# Rectifier.net
KiCad netlist of a schematic drawn in Altium Designer
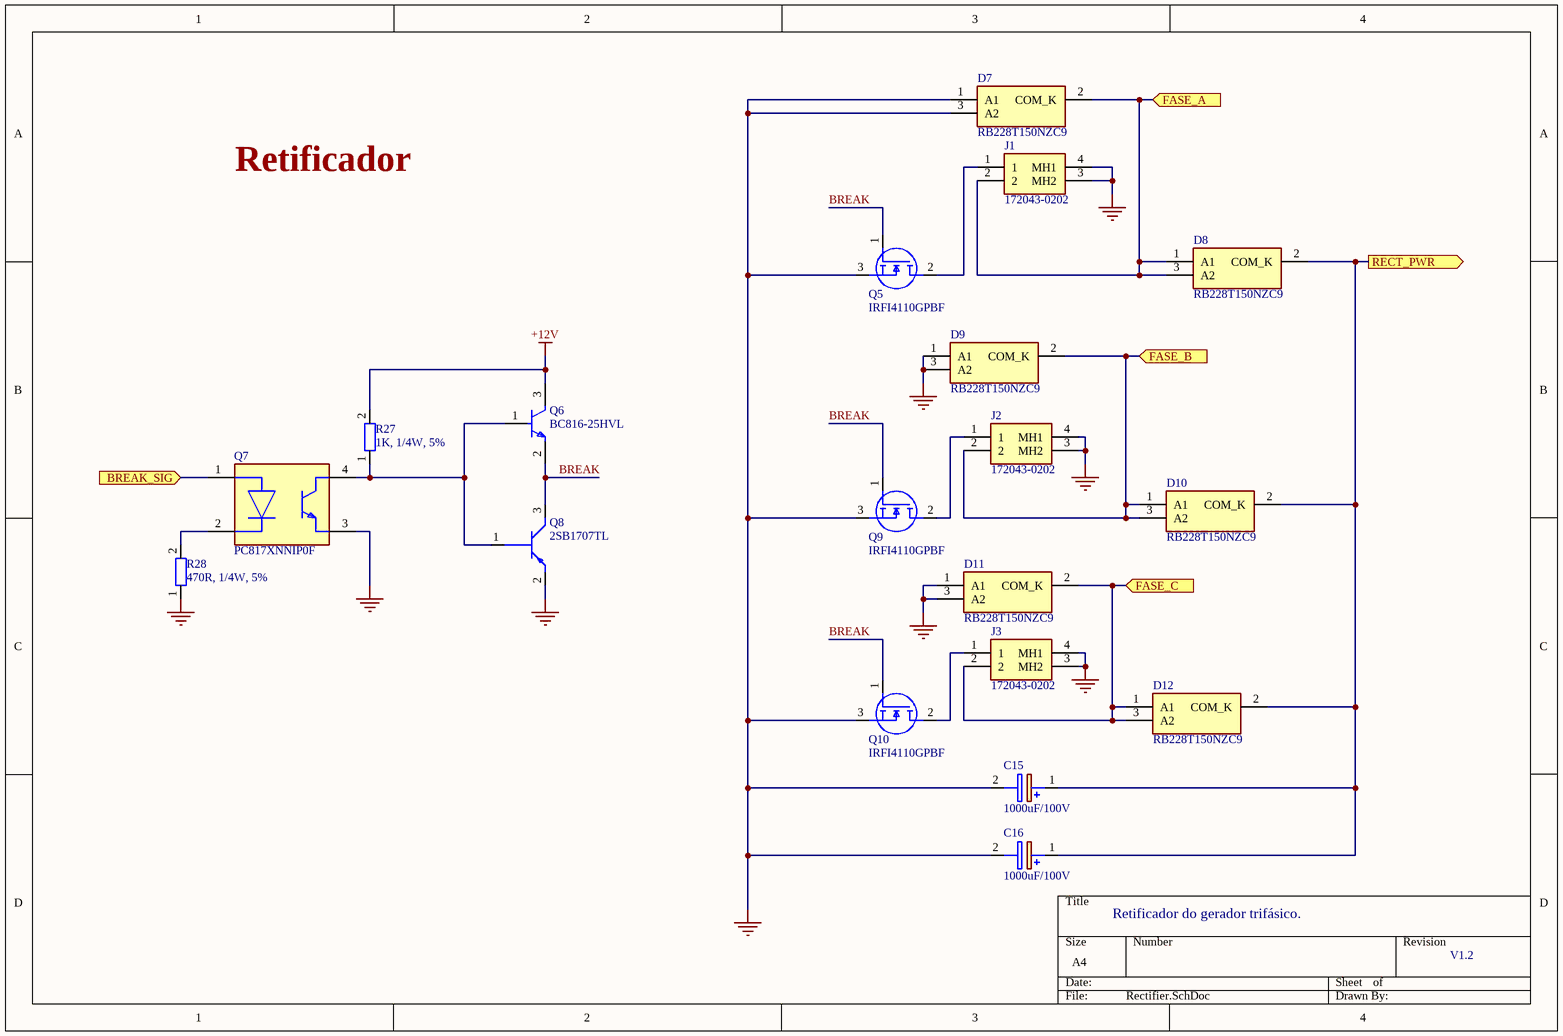
[diagram p0: Rectifier.SchDoc]

(export (version "E")
  (design (tool "Eeschema 10.0.6"))
  (components
    (comp (ref "C15")
      (value "1000uF/100V")
      (footprint "PcbLib1:CAPPRD750W85D1800H3750")
      (description "Aluminum Electrolytic Capacitors - Leaded 1000uF 100V")
      (fields
        (field (name "MANUFACTURER_PART_NUMBER") "ECA-2AHG102")
        (field (name "MOUSER PART NUMBER") "667-ECA-2AHG102")
      )
      (libsource (lib "*") (part "ECA-2AHG102"))
    )
    (comp (ref "C16")
      (value "1000uF/100V")
      (footprint "PcbLib1:CAPPRD750W85D1800H3750")
      (description "Aluminum Electrolytic Capacitors - Leaded 1000uF 100V")
      (fields
        (field (name "MANUFACTURER_PART_NUMBER") "ECA-2AHG102")
        (field (name "MOUSER PART NUMBER") "667-ECA-2AHG102")
      )
      (libsource (lib "*") (part "ECA-2AHG102"))
    )
    (comp (ref "D7")
      (value "RB228T150NZC9")
      (footprint "PcbLib1:TO254P480X1010X2100-3P")
      (description "Schottky Diode")
      (fields (field (name "MANUFACTURER") "Rohm"))
      (libsource (lib "pi2") (part "RB228T150NZC9"))
    )
    (comp (ref "D8")
      (value "RB228T150NZC9")
      (footprint "PcbLib1:TO254P480X1010X2100-3P")
      (description "Schottky Diode")
      (fields (field (name "MANUFACTURER") "Rohm"))
      (libsource (lib "pi2") (part "RB228T150NZC9"))
    )
    (comp (ref "D9")
      (value "RB228T150NZC9")
      (footprint "PcbLib1:TO254P480X1010X2100-3P")
      (description "Schottky Diode")
      (fields (field (name "MANUFACTURER") "Rohm"))
      (libsource (lib "pi2") (part "RB228T150NZC9"))
    )
    (comp (ref "D10")
      (value "RB228T150NZC9")
      (footprint "PcbLib1:TO254P480X1010X2100-3P")
      (description "Schottky Diode")
      (fields (field (name "MANUFACTURER") "Rohm"))
      (libsource (lib "pi2") (part "RB228T150NZC9"))
    )
    (comp (ref "D11")
      (value "RB228T150NZC9")
      (footprint "PcbLib1:TO254P480X1010X2100-3P")
      (description "Schottky Diode")
      (fields (field (name "MANUFACTURER") "Rohm"))
      (libsource (lib "pi2") (part "RB228T150NZC9"))
    )
    (comp (ref "D12")
      (value "RB228T150NZC9")
      (footprint "PcbLib1:TO254P480X1010X2100-3P")
      (description "Schottky Diode")
      (fields (field (name "MANUFACTURER") "Rohm"))
      (libsource (lib "pi2") (part "RB228T150NZC9"))
    )
    (comp (ref "J1")
      (value "172043-0202")
      (footprint "PcbLib1:1720430202")
      (description "CONN HDR 2POS 7.50MM R/A SLDR")
      (fields (field (name "MOUSER PART NUMBER") "538-172043-0202") (field (name "MANUFACTURER") "Molex"))
      (libsource (lib "pi2") (part "172043-0202"))
    )
    (comp (ref "J2")
      (value "172043-0202")
      (footprint "PcbLib1:1720430202")
      (description "CONN HDR 2POS 7.50MM R/A SLDR")
      (fields (field (name "MOUSER PART NUMBER") "538-172043-0202") (field (name "MANUFACTURER") "Molex"))
      (libsource (lib "pi2") (part "172043-0202"))
    )
    (comp (ref "J3")
      (value "172043-0202")
      (footprint "PcbLib1:1720430202")
      (description "CONN HDR 2POS 7.50MM R/A SLDR")
      (fields (field (name "MOUSER PART NUMBER") "538-172043-0202") (field (name "MANUFACTURER") "Molex"))
      (libsource (lib "pi2") (part "172043-0202"))
    )
    (comp (ref "Q5")
      (value "IRFI4110GPBF")
      (footprint "PcbLib1:TO254P483X1018X2095-3P")
      (description "MOSFET N-CH 100V 72A TO220AB")
      (fields (field (name "MOUSER PART NUMBER") "942-IRFI4110GPBF") (field (name "MANUFACTURER") "Infineon"))
      (libsource (lib "*") (part "IRFI4110GPBF"))
    )
    (comp (ref "Q6")
      (value "BC816-25HVL")
      (footprint "FP-SOT23-IPC_C")
      (description "BC816-25H/SOT23/TO-236AB")
      (fields (field (name "MANUFACTURER") "Nexperia"))
      (libsource (lib "Altium Content Vault") (part "9d60fdc623e8f58b3f4e6ee889b877a"))
    )
    (comp (ref "Q7")
      (value "PC817XNNIP0F")
      (footprint "FP-PC817XNNIP0F-MFG")
      (description "OPTOISOLATOR 5KV TRANS 4SMD")
      (fields (field (name "MANUFACTURER") "Sharp"))
      (libsource (lib "Altium Content Vault") (part "6470904bf6395c62928ee73e60120b8"))
    )
    (comp (ref "Q8")
      (value "2SB1707TL")
      (footprint "PcbLib1:SOT95P280X100-3N")
      (description "TRANS PNP 12V 4A TSMT3")
      (fields (field (name "MOUSER PART NUMBER") "755-2SB1707TL") (field (name "MANUFACTURER") "Rohm"))
      (libsource (lib "pi2") (part "2SB1707TL"))
    )
    (comp (ref "Q9")
      (value "IRFI4110GPBF")
      (footprint "PcbLib1:TO254P483X1018X2095-3P")
      (description "MOSFET N-CH 100V 72A TO220AB")
      (fields (field (name "MOUSER PART NUMBER") "942-IRFI4110GPBF") (field (name "MANUFACTURER") "Infineon"))
      (libsource (lib "*") (part "IRFI4110GPBF"))
    )
    (comp (ref "Q10")
      (value "IRFI4110GPBF")
      (footprint "PcbLib1:TO254P483X1018X2095-3P")
      (description "MOSFET N-CH 100V 72A TO220AB")
      (fields (field (name "MOUSER PART NUMBER") "942-IRFI4110GPBF") (field (name "MANUFACTURER") "Infineon"))
      (libsource (lib "*") (part "IRFI4110GPBF"))
    )
    (comp (ref "R27")
      (value "1K, 1/4W, 5%")
      (footprint "PcbLib1:RES-0805")
      (description "Res General Purpose Thick Film 0805 1k Ohm 5% 1/4W ±200ppm/°C Molded Paper T/R")
      (fields
        (field (name "MANUFACTURER_PART_NUMBER") "RC0805JR-131KL")
        (field (name "MOUSER PART NUMBER") "603-RC0805JR-131KL")
      )
      (libsource (lib "pi2") (part "Res-0805"))
    )
    (comp (ref "R28")
      (value "470R, 1/4W, 5%")
      (footprint "PcbLib1:RES-0805")
      (description "Thick Film Resistors - SMD 470 OHM 5%")
      (fields
        (field (name "MANUFACTURER_PART_NUMBER") "RC0805JR-131KL")
        (field (name "MOUSER PART NUMBER") "603-RC0805JR-131KL")
      )
      (libsource (lib "pi2") (part "Res-0805"))
    )
  )
  (nets
    (net (code "1") (name "+12V") (class "Default")
      (node (ref "Q6") (pin "3") (pinfunction "C_3") (pintype "passive"))
      (node (ref "R27") (pin "2") (pinfunction "2_2") (pintype "passive"))
    )
    (net (code "2") (name "/BREAK") (class "Default")
      (node (ref "Q10") (pin "1") (pinfunction "G_1") (pintype "passive"))
      (node (ref "Q5") (pin "1") (pinfunction "G_1") (pintype "passive"))
      (node (ref "Q6") (pin "2") (pinfunction "E_2") (pintype "passive"))
      (node (ref "Q8") (pin "3") (pinfunction "C_3") (pintype "passive"))
      (node (ref "Q9") (pin "1") (pinfunction "G_1") (pintype "passive"))
    )
    (net (code "3") (name "/BREAK_SIG") (class "Default")
      (node (ref "Q7") (pin "1") (pinfunction "A_1") (pintype "passive"))
    )
    (net (code "4") (name "/FASE_A") (class "Default")
      (node (ref "D7") (pin "2") (pinfunction "COM_K_2") (pintype "passive"))
      (node (ref "D8") (pin "1") (pinfunction "A1_1") (pintype "passive"))
      (node (ref "D8") (pin "3") (pinfunction "A2_3") (pintype "passive"))
      (node (ref "J1") (pin "2") (pinfunction "2_2") (pintype "passive"))
    )
    (net (code "5") (name "/FASE_B") (class "Default")
      (node (ref "D10") (pin "1") (pinfunction "A1_1") (pintype "passive"))
      (node (ref "D10") (pin "3") (pinfunction "A2_3") (pintype "passive"))
      (node (ref "D9") (pin "2") (pinfunction "COM_K_2") (pintype "passive"))
      (node (ref "J2") (pin "2") (pinfunction "2_2") (pintype "passive"))
    )
    (net (code "6") (name "/FASE_C") (class "Default")
      (node (ref "D11") (pin "2") (pinfunction "COM_K_2") (pintype "passive"))
      (node (ref "D12") (pin "1") (pinfunction "A1_1") (pintype "passive"))
      (node (ref "D12") (pin "3") (pinfunction "A2_3") (pintype "passive"))
      (node (ref "J3") (pin "2") (pinfunction "2_2") (pintype "passive"))
    )
    (net (code "7") (name "/RECT_PWR") (class "Default")
      (node (ref "C15") (pin "1") (pinfunction "+_1") (pintype "passive"))
      (node (ref "C16") (pin "1") (pinfunction "+_1") (pintype "passive"))
      (node (ref "D10") (pin "2") (pinfunction "COM_K_2") (pintype "passive"))
      (node (ref "D12") (pin "2") (pinfunction "COM_K_2") (pintype "passive"))
      (node (ref "D8") (pin "2") (pinfunction "COM_K_2") (pintype "passive"))
    )
    (net (code "8") (name "GND") (class "Default")
      (node (ref "C15") (pin "2") (pinfunction "-_2") (pintype "passive"))
      (node (ref "C16") (pin "2") (pinfunction "-_2") (pintype "passive"))
      (node (ref "D11") (pin "1") (pinfunction "A1_1") (pintype "passive"))
      (node (ref "D11") (pin "3") (pinfunction "A2_3") (pintype "passive"))
      (node (ref "D7") (pin "1") (pinfunction "A1_1") (pintype "passive"))
      (node (ref "D7") (pin "3") (pinfunction "A2_3") (pintype "passive"))
      (node (ref "D9") (pin "1") (pinfunction "A1_1") (pintype "passive"))
      (node (ref "D9") (pin "3") (pinfunction "A2_3") (pintype "passive"))
      (node (ref "J1") (pin "3") (pinfunction "MH2_3") (pintype "passive"))
      (node (ref "J1") (pin "4") (pinfunction "MH1_4") (pintype "passive"))
      (node (ref "J2") (pin "3") (pinfunction "MH2_3") (pintype "passive"))
      (node (ref "J2") (pin "4") (pinfunction "MH1_4") (pintype "passive"))
      (node (ref "J3") (pin "3") (pinfunction "MH2_3") (pintype "passive"))
      (node (ref "J3") (pin "4") (pinfunction "MH1_4") (pintype "passive"))
      (node (ref "Q10") (pin "3") (pinfunction "S_3") (pintype "passive"))
      (node (ref "Q5") (pin "3") (pinfunction "S_3") (pintype "passive"))
      (node (ref "Q7") (pin "3") (pinfunction "E_3") (pintype "passive"))
      (node (ref "Q8") (pin "2") (pinfunction "E_2") (pintype "passive"))
      (node (ref "Q9") (pin "3") (pinfunction "S_3") (pintype "passive"))
      (node (ref "R28") (pin "1") (pinfunction "1_1") (pintype "passive"))
    )
    (net (code "9") (name "Net-(Q5-D)") (class "Default")
      (node (ref "J1") (pin "1") (pinfunction "1_1") (pintype "passive"))
      (node (ref "Q5") (pin "2") (pinfunction "D_2") (pintype "passive"))
    )
    (net (code "10") (name "Net-(Q6-B)") (class "Default")
      (node (ref "Q6") (pin "1") (pinfunction "B_1") (pintype "passive"))
      (node (ref "Q7") (pin "4") (pinfunction "C_4") (pintype "passive"))
      (node (ref "Q8") (pin "1") (pinfunction "B_1") (pintype "passive"))
      (node (ref "R27") (pin "1") (pinfunction "1_1") (pintype "passive"))
    )
    (net (code "11") (name "Net-(Q7-C-Pad2)") (class "Default")
      (node (ref "Q7") (pin "2") (pinfunction "C_2") (pintype "passive"))
      (node (ref "R28") (pin "2") (pinfunction "2_2") (pintype "passive"))
    )
    (net (code "12") (name "Net-(Q9-D)") (class "Default")
      (node (ref "J2") (pin "1") (pinfunction "1_1") (pintype "passive"))
      (node (ref "Q9") (pin "2") (pinfunction "D_2") (pintype "passive"))
    )
    (net (code "13") (name "Net-(Q10-D)") (class "Default")
      (node (ref "J3") (pin "1") (pinfunction "1_1") (pintype "passive"))
      (node (ref "Q10") (pin "2") (pinfunction "D_2") (pintype "passive"))
    )
  )
)
